# frm-voltrod_main.net
KiCad netlist of a schematic drawn in Altium Designer
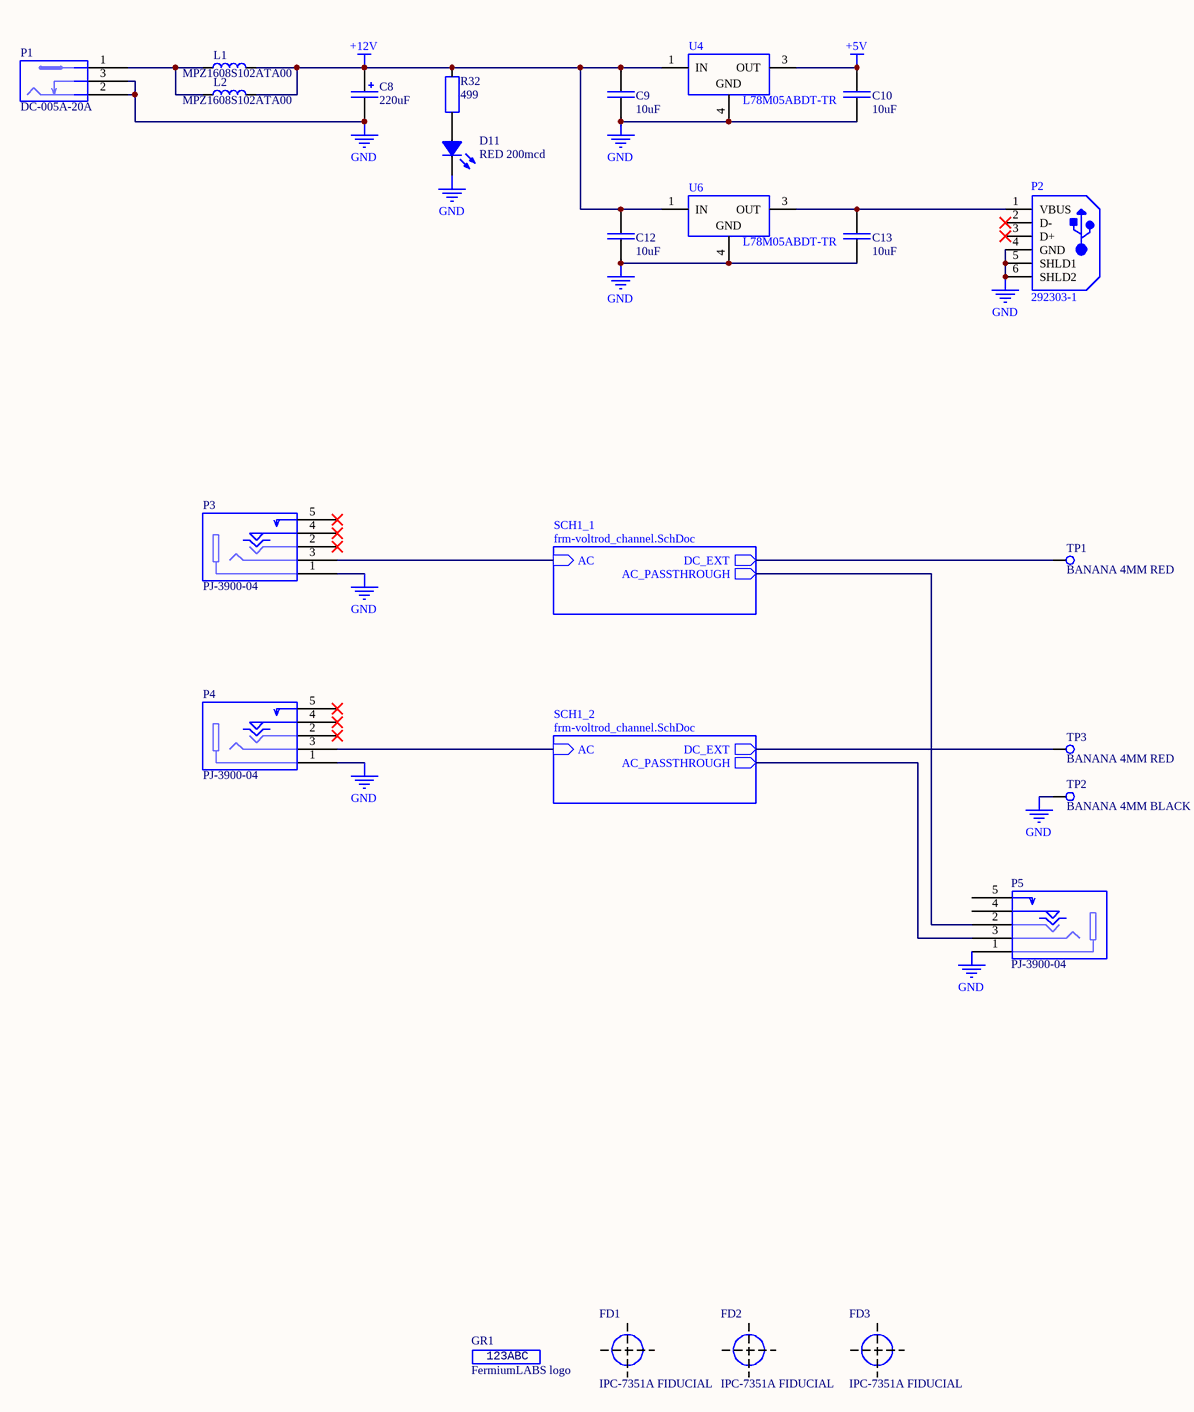
[diagram p0: frm-voltrod_main.SchDoc]

(export (version "E")
  (design (tool "Eeschema 10.0.6"))
  (components
    (comp (ref "C8")
      (value "220uF")
      (footprint "3924B366-8672-45E9-B0BE-62DACC24E783")
      (description "CAP  THT ELEC 220uF 25V 20%")
      (fields (field (name "PART NUMBER") "1a28df19-6d3e-4a71-836c-f22920f8e8ab"))
      (libsource (lib "frmdblib") (part "GENERIC_C_ELEC"))
    )
    (comp (ref "C9")
      (value "10uF")
      (footprint "CAP 0805_2012")
      (description "CAP SMD MLCC 10uF 25V 0805 X5R")
      (fields (field (name "PART NUMBER") "1ffbe5a9-0884-4740-bdad-20a6a98400e6"))
      (libsource (lib "frmdblib") (part "GENERIC_C"))
    )
    (comp (ref "C10")
      (value "10uF")
      (footprint "CAP 0805_2012")
      (description "CAP SMD MLCC 10uF 25V 0805 X5R")
      (fields (field (name "PART NUMBER") "1ffbe5a9-0884-4740-bdad-20a6a98400e6"))
      (libsource (lib "frmdblib") (part "GENERIC_C"))
    )
    (comp (ref "C12")
      (value "10uF")
      (footprint "CAP 0805_2012")
      (description "CAP SMD MLCC 10uF 25V 0805 X5R")
      (fields (field (name "PART NUMBER") "1ffbe5a9-0884-4740-bdad-20a6a98400e6"))
      (libsource (lib "frmdblib") (part "GENERIC_C"))
    )
    (comp (ref "C13")
      (value "10uF")
      (footprint "CAP 0805_2012")
      (description "CAP SMD MLCC 10uF 25V 0805 X5R")
      (fields (field (name "PART NUMBER") "1ffbe5a9-0884-4740-bdad-20a6a98400e6"))
      (libsource (lib "frmdblib") (part "GENERIC_C"))
    )
    (comp (ref "D11")
      (value "RED 200mcd")
      (footprint "ED49B4F6-595F-4D62-96BB-D7184CAA9B94")
      (description "DIODE LED THT 5MM RED 200mcd")
      (fields (field (name "PART NUMBER") "c65ae3d2-9539-4634-8979-616a331b7494"))
      (libsource (lib "frmdblib") (part "GENERIC_D_LED"))
    )
    (comp (ref "FD1")
      (value "IPC-7351A FIDUCIAL")
      (footprint "FIDUCIAL-IPC-7351A")
      (description "GRAPHICS FIDUCIAL IPC-7351A")
      (fields (field (name "PART NUMBER") "19da4612-eb95-43bb-9984-553a52b2a224"))
      (libsource (lib "frmdblib") (part "GENERIC_FIDUCIAL"))
    )
    (comp (ref "FD2")
      (value "IPC-7351A FIDUCIAL")
      (footprint "FIDUCIAL-IPC-7351A")
      (description "GRAPHICS FIDUCIAL IPC-7351A")
      (fields (field (name "PART NUMBER") "19da4612-eb95-43bb-9984-553a52b2a224"))
      (libsource (lib "frmdblib") (part "GENERIC_FIDUCIAL"))
    )
    (comp (ref "FD3")
      (value "IPC-7351A FIDUCIAL")
      (footprint "FIDUCIAL-IPC-7351A")
      (description "GRAPHICS FIDUCIAL IPC-7351A")
      (fields (field (name "PART NUMBER") "19da4612-eb95-43bb-9984-553a52b2a224"))
      (libsource (lib "frmdblib") (part "GENERIC_FIDUCIAL"))
    )
    (comp (ref "GR1")
      (value "FermiumLABS logo")
      (footprint "5394DE47-A0E8-4329-8464-7791B7C19310")
      (description "GRAPHICS LOGO FERMIUM LABS SRL")
      (fields (field (name "PART NUMBER") "50f8ea88-0034-49fe-a263-d8e97bc35e2f"))
      (libsource (lib "frmdblib") (part "GENERIC_GRAPHIC"))
    )
    (comp (ref "L1")
      (value "MPZ1608S102ATA00")
      (footprint "FER 0603_1608")
      (description "FER SMD CHIP 0603 800mA 1K@100MHz 300mOhm")
      (fields (field (name "PART NUMBER") "a4b2e015-bf25-47b8-954c-a5b040744a3a"))
      (libsource (lib "frmdblib") (part "GENERIC_L"))
    )
    (comp (ref "L2")
      (value "MPZ1608S102ATA00")
      (footprint "FER 0603_1608")
      (description "FER SMD CHIP 0603 800mA 1K@100MHz 300mOhm")
      (fields (field (name "PART NUMBER") "a4b2e015-bf25-47b8-954c-a5b040744a3a"))
      (libsource (lib "frmdblib") (part "GENERIC_L"))
    )
    (comp (ref "P1")
      (value "DC-005A-20A")
      (footprint "F0972D8A-C5C0-4A84-836D-A9666EE65C2D")
      (description "CONN THT DC JACK 0.5A 30VDC 5Kcycles")
      (fields (field (name "PART NUMBER") "b53db51a-1725-412b-9039-fa7a45c7c438"))
      (libsource (lib "frmdblib") (part "34A1CD0B-E262-46EF-B9F1-39CB809C308F"))
    )
    (comp (ref "P2")
      (value "292303-1")
      (footprint "8A51F738-712D-4EE5-9D6B-BB16603F834E")
      (description "CONN THT USB TYPE-A HIGH RELIABILITY")
      (fields (field (name "PART NUMBER") "9ff2a560-e541-4da0-adda-013cc9c65511"))
      (libsource (lib "frmdblib") (part "19C864C6-9E55-4731-863D-CE3C8E5D2E63"))
    )
    (comp (ref "P3")
      (value "PJ-3900-04")
      (footprint "7EF2B92C-0FC9-4C85-B662-5CEC65BFCCC4")
      (description "CONN THT 3.5mm AUDIO STEREO AUX SWITCH")
      (fields (field (name "PART NUMBER") "80507a24-5d7c-4cf5-953e-f54832d54564"))
      (libsource (lib "frmdblib") (part "46E41D2F-79BD-46AC-B778-70B2D50A946A"))
    )
    (comp (ref "P4")
      (value "PJ-3900-04")
      (footprint "7EF2B92C-0FC9-4C85-B662-5CEC65BFCCC4")
      (description "CONN THT 3.5mm AUDIO STEREO AUX SWITCH")
      (fields (field (name "PART NUMBER") "80507a24-5d7c-4cf5-953e-f54832d54564"))
      (libsource (lib "frmdblib") (part "46E41D2F-79BD-46AC-B778-70B2D50A946A"))
    )
    (comp (ref "P5")
      (value "PJ-3900-04")
      (footprint "7EF2B92C-0FC9-4C85-B662-5CEC65BFCCC4")
      (description "CONN THT 3.5mm AUDIO STEREO AUX SWITCH")
      (fields (field (name "PART NUMBER") "80507a24-5d7c-4cf5-953e-f54832d54564"))
      (libsource (lib "") (part "46E41D2F-79BD-46AC-B778-70B2D50A946A_1"))
    )
    (comp (ref "R32")
      (value "499")
      (footprint "RES 1206_3216")
      (description "RES SMD 499 OHM 1% 1/4W 1206")
      (fields (field (name "PART NUMBER") "c8bf8de8-3430-48dd-94ac-a027709c0c4f"))
      (libsource (lib "frmdblib") (part "GENERIC_R"))
    )
    (comp (ref "TP1")
      (value "BANANA 4MM RED")
      (footprint "2382AA2C-2335-4562-94C7-3B9045982126")
      (description "CONN BANANA SOCKET 4MM RED")
      (fields (field (name "PART NUMBER") "3b84d3c9-1de5-4004-b768-3958a778153b"))
      (libsource (lib "frmdblib") (part "GENERIC_TP"))
    )
    (comp (ref "TP2")
      (value "BANANA 4MM BLACK")
      (footprint "2382AA2C-2335-4562-94C7-3B9045982126")
      (description "CONN BANANA SOCKET 4MM BLACK")
      (fields (field (name "PART NUMBER") "80ef162c-aaff-440a-80ad-5900ce15f9c1"))
      (libsource (lib "frmdblib") (part "GENERIC_TP"))
    )
    (comp (ref "TP3")
      (value "BANANA 4MM RED")
      (footprint "2382AA2C-2335-4562-94C7-3B9045982126")
      (description "CONN BANANA SOCKET 4MM RED")
      (fields (field (name "PART NUMBER") "3b84d3c9-1de5-4004-b768-3958a778153b"))
      (libsource (lib "frmdblib") (part "GENERIC_TP"))
    )
    (comp (ref "U4")
      (value "L78M05ABDT-TR")
      (footprint "4BDA507D-BB70-4009-B963-85AD90086B51")
      (description "IC SMD LINEAR VOLTAGE REGULATOR 5V 500mA DPAK/TO-252")
      (fields (field (name "PART NUMBER") "446536aa-1bdd-4764-8cae-49f4e0c126ff"))
      (libsource (lib "frmdblib") (part "568C7F7F-B71D-457E-B5FB-AE9D42DA8928"))
    )
    (comp (ref "U6")
      (value "L78M05ABDT-TR")
      (footprint "4BDA507D-BB70-4009-B963-85AD90086B51")
      (description "IC SMD LINEAR VOLTAGE REGULATOR 5V 500mA DPAK/TO-252")
      (fields (field (name "PART NUMBER") "446536aa-1bdd-4764-8cae-49f4e0c126ff"))
      (libsource (lib "frmdblib") (part "568C7F7F-B71D-457E-B5FB-AE9D42DA8928"))
    )
  )
  (nets
    (net (code "1") (name "+5V") (class "Default")
      (node (ref "C10") (pin "1") (pintype "passive"))
      (node (ref "U4") (pin "3") (pinfunction "OUT_3") (pintype "power_in"))
    )
    (net (code "2") (name "+12V") (class "Default")
      (node (ref "C12") (pin "1") (pintype "passive"))
      (node (ref "C8") (pin "1") (pintype "passive"))
      (node (ref "C9") (pin "1") (pintype "passive"))
      (node (ref "L1") (pin "2") (pintype "passive"))
      (node (ref "L2") (pin "2") (pintype "passive"))
      (node (ref "R32") (pin "2") (pintype "passive"))
      (node (ref "U4") (pin "1") (pinfunction "IN_1") (pintype "power_in"))
      (node (ref "U6") (pin "1") (pinfunction "IN_1") (pintype "power_in"))
    )
    (net (code "3") (name "/AC") (class "Default")
      (node (ref "P4") (pin "3") (pinfunction "L_3") (pintype "passive"))
    )
    (net (code "4") (name "/AC_1") (class "Default")
      (node (ref "P3") (pin "3") (pinfunction "L_3") (pintype "passive"))
    )
    (net (code "5") (name "/AC_PASSTHROUGH") (class "Default")
      (node (ref "P5") (pin "3") (pinfunction "L_3") (pintype "passive"))
    )
    (net (code "6") (name "/AC_PASSTHROUGH_1") (class "Default")
      (node (ref "P5") (pin "2") (pinfunction "R_2") (pintype "passive"))
    )
    (net (code "7") (name "/DC_EXT") (class "Default")
      (node (ref "TP3") (pin "1") (pinfunction "TP_1") (pintype "passive"))
    )
    (net (code "8") (name "/DC_EXT_1") (class "Default")
      (node (ref "TP1") (pin "1") (pinfunction "TP_1") (pintype "passive"))
    )
    (net (code "9") (name "GND") (class "Default")
      (node (ref "C10") (pin "2") (pintype "passive"))
      (node (ref "C12") (pin "2") (pintype "passive"))
      (node (ref "C13") (pin "2") (pintype "passive"))
      (node (ref "C8") (pin "2") (pintype "passive"))
      (node (ref "C9") (pin "2") (pintype "passive"))
      (node (ref "D11") (pin "1") (pinfunction "K_1") (pintype "passive"))
      (node (ref "P1") (pin "2") (pinfunction "2_2") (pintype "passive"))
      (node (ref "P1") (pin "3") (pinfunction "3_3") (pintype "passive"))
      (node (ref "P2") (pin "4") (pinfunction "GND_4") (pintype "passive"))
      (node (ref "P2") (pin "5") (pinfunction "SHLD1_5") (pintype "passive"))
      (node (ref "P2") (pin "6") (pinfunction "SHLD2_6") (pintype "passive"))
      (node (ref "P3") (pin "1") (pinfunction "GND_1") (pintype "passive"))
      (node (ref "P4") (pin "1") (pinfunction "GND_1") (pintype "passive"))
      (node (ref "P5") (pin "1") (pinfunction "GND_1") (pintype "passive"))
      (node (ref "TP2") (pin "1") (pinfunction "TP_1") (pintype "passive"))
      (node (ref "U4") (pin "4") (pinfunction "GND_4") (pintype "power_in"))
      (node (ref "U6") (pin "4") (pinfunction "GND_4") (pintype "power_in"))
    )
    (net (code "10") (name "Net-(D11-A)") (class "Default")
      (node (ref "D11") (pin "2") (pinfunction "A_2") (pintype "passive"))
      (node (ref "R32") (pin "1") (pintype "passive"))
    )
    (net (code "11") (name "Net-(L1-Pad1)") (class "Default")
      (node (ref "L1") (pin "1") (pintype "passive"))
      (node (ref "L2") (pin "1") (pintype "passive"))
      (node (ref "P1") (pin "1") (pinfunction "1_1") (pintype "passive"))
    )
    (net (code "12") (name "Net-(P2-VBUS)") (class "Default")
      (node (ref "C13") (pin "1") (pintype "passive"))
      (node (ref "P2") (pin "1") (pinfunction "VBUS_1") (pintype "passive"))
      (node (ref "U6") (pin "3") (pinfunction "OUT_3") (pintype "power_in"))
    )
    (net (code "13") (name "unconnected-(P2-D+-Pad3)") (class "Default")
      (node (ref "P2") (pin "3") (pinfunction "D+_3") (pintype "passive+no_connect"))
    )
    (net (code "14") (name "unconnected-(P2-D--Pad2)") (class "Default")
      (node (ref "P2") (pin "2") (pinfunction "D-_2") (pintype "passive+no_connect"))
    )
    (net (code "15") (name "unconnected-(P3-AUX-Pad4)") (class "Default")
      (node (ref "P3") (pin "4") (pinfunction "AUX_4") (pintype "passive+no_connect"))
    )
    (net (code "16") (name "unconnected-(P3-AUX-Pad5)") (class "Default")
      (node (ref "P3") (pin "5") (pinfunction "AUX_5") (pintype "passive+no_connect"))
    )
    (net (code "17") (name "unconnected-(P3-R-Pad2)") (class "Default")
      (node (ref "P3") (pin "2") (pinfunction "R_2") (pintype "passive+no_connect"))
    )
    (net (code "18") (name "unconnected-(P4-AUX-Pad4)") (class "Default")
      (node (ref "P4") (pin "4") (pinfunction "AUX_4") (pintype "passive+no_connect"))
    )
    (net (code "19") (name "unconnected-(P4-AUX-Pad5)") (class "Default")
      (node (ref "P4") (pin "5") (pinfunction "AUX_5") (pintype "passive+no_connect"))
    )
    (net (code "20") (name "unconnected-(P4-R-Pad2)") (class "Default")
      (node (ref "P4") (pin "2") (pinfunction "R_2") (pintype "passive+no_connect"))
    )
    (net (code "21") (name "unconnected-(P5-AUX-Pad4)") (class "Default")
      (node (ref "P5") (pin "4") (pinfunction "AUX_4") (pintype "passive"))
    )
    (net (code "22") (name "unconnected-(P5-AUX-Pad5)") (class "Default")
      (node (ref "P5") (pin "5") (pinfunction "AUX_5") (pintype "passive"))
    )
  )
)
